# frets-input2.net
KiCad netlist of a schematic drawn in EAGLE
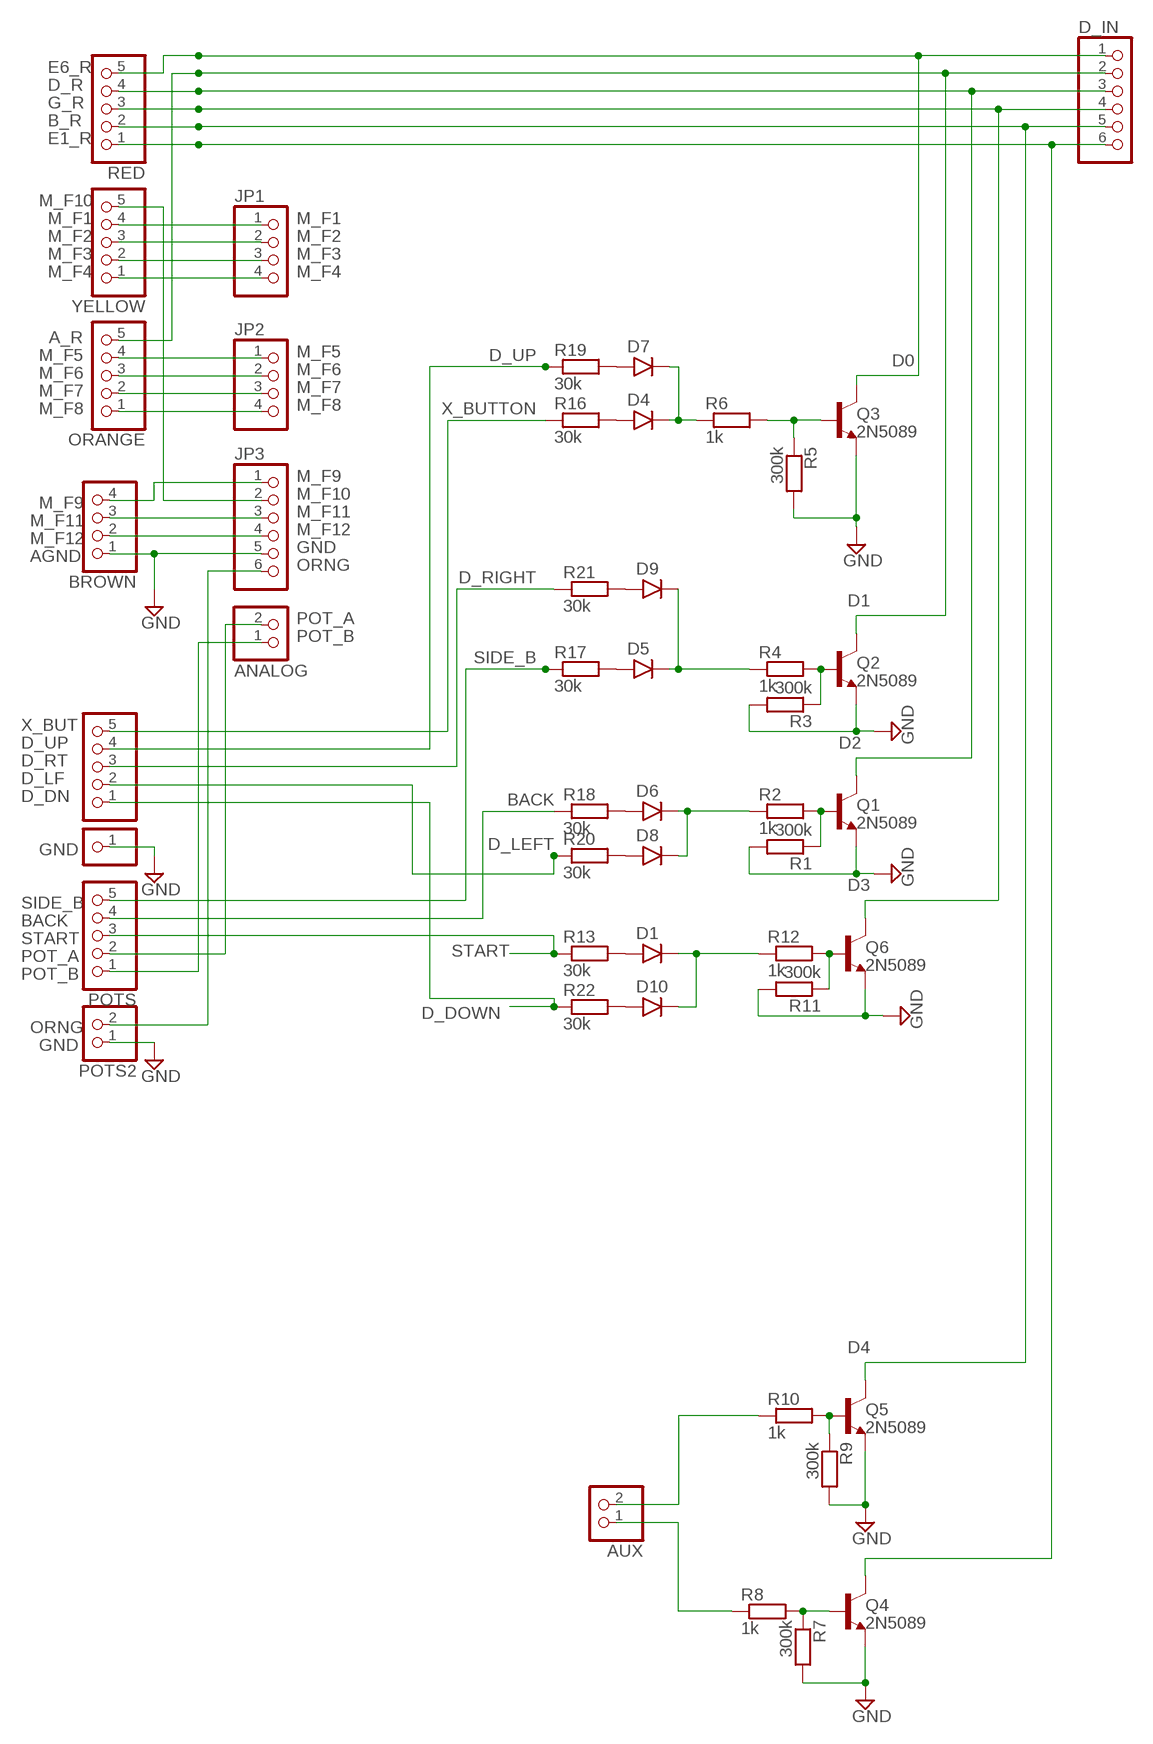
[diagram p0: schematic, sheet 1]

(export (version "E")
  (design (tool "Eeschema 10.0.6"))
  (components
    (comp (ref "ANALOG")
      (value "PINHD-1X2")
      (footprint "eagle-import:1X02")
      (libsource (lib "eagle-import") (part "PINHD-1X2"))
    )
    (comp (ref "AUX")
      (value "PINHD-1X2")
      (footprint "eagle-import:1X02")
      (libsource (lib "eagle-import") (part "PINHD-1X2"))
    )
    (comp (ref "BROWN")
      (value "PINHD-1X4")
      (footprint "eagle-import:1X04")
      (libsource (lib "eagle-import") (part "PINHD-1X4"))
    )
    (comp (ref "D1")
      (value "1N4148-4")
      (footprint "eagle-import:DO35-4")
      (libsource (lib "eagle-import") (part "1N4148-4"))
    )
    (comp (ref "D4")
      (value "1N4148-2")
      (footprint "eagle-import:DO35-2")
      (libsource (lib "eagle-import") (part "1N4148-2"))
    )
    (comp (ref "D5")
      (value "1N4148-4")
      (footprint "eagle-import:DO35-4")
      (libsource (lib "eagle-import") (part "1N4148-4"))
    )
    (comp (ref "D6")
      (value "1N4148-2")
      (footprint "eagle-import:DO35-2")
      (libsource (lib "eagle-import") (part "1N4148-2"))
    )
    (comp (ref "D7")
      (value "1N4148-2")
      (footprint "eagle-import:DO35-2")
      (libsource (lib "eagle-import") (part "1N4148-2"))
    )
    (comp (ref "D8")
      (value "1N4148-2")
      (footprint "eagle-import:DO35-2")
      (libsource (lib "eagle-import") (part "1N4148-2"))
    )
    (comp (ref "D9")
      (value "1N4148-4")
      (footprint "eagle-import:DO35-4")
      (libsource (lib "eagle-import") (part "1N4148-4"))
    )
    (comp (ref "D10")
      (value "1N4148-2")
      (footprint "eagle-import:DO35-2")
      (libsource (lib "eagle-import") (part "1N4148-2"))
    )
    (comp (ref "DPAD")
      (value "PINHD-1X5")
      (footprint "eagle-import:1X05")
      (libsource (lib "eagle-import") (part "PINHD-1X5"))
    )
    (comp (ref "DPAD2")
      (value "PINHD-1X1")
      (footprint "eagle-import:1X01")
      (libsource (lib "eagle-import") (part "PINHD-1X1"))
    )
    (comp (ref "D_IN")
      (value "PINHD-1X6")
      (footprint "eagle-import:1X06")
      (libsource (lib "eagle-import") (part "PINHD-1X6"))
    )
    (comp (ref "JP1")
      (value "PINHD-1X4")
      (footprint "eagle-import:1X04")
      (libsource (lib "eagle-import") (part "PINHD-1X4"))
    )
    (comp (ref "JP2")
      (value "PINHD-1X4")
      (footprint "eagle-import:1X04")
      (libsource (lib "eagle-import") (part "PINHD-1X4"))
    )
    (comp (ref "JP3")
      (value "PINHD-1X6")
      (footprint "eagle-import:1X06")
      (libsource (lib "eagle-import") (part "PINHD-1X6"))
    )
    (comp (ref "ORANGE")
      (value "PINHD-1X5")
      (footprint "eagle-import:1X05")
      (libsource (lib "eagle-import") (part "PINHD-1X5"))
    )
    (comp (ref "POTS")
      (value "PINHD-1X5")
      (footprint "eagle-import:1X05")
      (libsource (lib "eagle-import") (part "PINHD-1X5"))
    )
    (comp (ref "POTS2")
      (value "PINHD-1X2")
      (footprint "eagle-import:1X02")
      (libsource (lib "eagle-import") (part "PINHD-1X2"))
    )
    (comp (ref "Q1")
      (value "2N5089")
      (footprint "eagle-import:TO92-")
      (libsource (lib "eagle-import") (part "2N5089"))
    )
    (comp (ref "Q2")
      (value "2N5089")
      (footprint "eagle-import:TO92-")
      (libsource (lib "eagle-import") (part "2N5089"))
    )
    (comp (ref "Q3")
      (value "2N5089")
      (footprint "eagle-import:TO92-")
      (libsource (lib "eagle-import") (part "2N5089"))
    )
    (comp (ref "Q4")
      (value "2N5089")
      (footprint "eagle-import:TO92-")
      (libsource (lib "eagle-import") (part "2N5089"))
    )
    (comp (ref "Q5")
      (value "2N5089")
      (footprint "eagle-import:TO92-")
      (libsource (lib "eagle-import") (part "2N5089"))
    )
    (comp (ref "Q6")
      (value "2N5089")
      (footprint "eagle-import:TO92-")
      (libsource (lib "eagle-import") (part "2N5089"))
    )
    (comp (ref "R1")
      (value "300k")
      (footprint "eagle-import:R0207_1V")
      (libsource (lib "eagle-import") (part "6MM-EU1"))
    )
    (comp (ref "R2")
      (value "1k")
      (footprint "eagle-import:R0207_3")
      (libsource (lib "eagle-import") (part "6MM-EU"))
    )
    (comp (ref "R3")
      (value "300k")
      (footprint "eagle-import:R0207_1V")
      (libsource (lib "eagle-import") (part "6MM-EU1"))
    )
    (comp (ref "R4")
      (value "1k")
      (footprint "eagle-import:R0207_3")
      (libsource (lib "eagle-import") (part "6MM-EU"))
    )
    (comp (ref "R5")
      (value "300k")
      (footprint "eagle-import:R0207_1V")
      (libsource (lib "eagle-import") (part "6MM-EU1"))
    )
    (comp (ref "R6")
      (value "1k")
      (footprint "eagle-import:R0207_3")
      (libsource (lib "eagle-import") (part "6MM-EU"))
    )
    (comp (ref "R7")
      (value "300k")
      (footprint "eagle-import:R0207_1V")
      (libsource (lib "eagle-import") (part "6MM-EU1"))
    )
    (comp (ref "R8")
      (value "1k")
      (footprint "eagle-import:R0207_3")
      (libsource (lib "eagle-import") (part "6MM-EU"))
    )
    (comp (ref "R9")
      (value "300k")
      (footprint "eagle-import:R0207_1V")
      (libsource (lib "eagle-import") (part "6MM-EU1"))
    )
    (comp (ref "R10")
      (value "1k")
      (footprint "eagle-import:R0207_3")
      (libsource (lib "eagle-import") (part "6MM-EU"))
    )
    (comp (ref "R11")
      (value "300k")
      (footprint "eagle-import:R0207_1V")
      (libsource (lib "eagle-import") (part "6MM-EU1"))
    )
    (comp (ref "R12")
      (value "1k")
      (footprint "eagle-import:R0207_3")
      (libsource (lib "eagle-import") (part "6MM-EU"))
    )
    (comp (ref "R13")
      (value "30k")
      (footprint "eagle-import:R0207_3")
      (libsource (lib "eagle-import") (part "6MM-EU"))
    )
    (comp (ref "R16")
      (value "30k")
      (footprint "eagle-import:R0207_3")
      (libsource (lib "eagle-import") (part "6MM-EU"))
    )
    (comp (ref "R17")
      (value "30k")
      (footprint "eagle-import:R0207_3")
      (libsource (lib "eagle-import") (part "6MM-EU"))
    )
    (comp (ref "R18")
      (value "30k")
      (footprint "eagle-import:R0207_3")
      (libsource (lib "eagle-import") (part "6MM-EU"))
    )
    (comp (ref "R19")
      (value "30k")
      (footprint "eagle-import:R0207_3")
      (libsource (lib "eagle-import") (part "6MM-EU"))
    )
    (comp (ref "R20")
      (value "30k")
      (footprint "eagle-import:R0207_3")
      (libsource (lib "eagle-import") (part "6MM-EU"))
    )
    (comp (ref "R21")
      (value "30k")
      (footprint "eagle-import:R0207_3")
      (libsource (lib "eagle-import") (part "6MM-EU"))
    )
    (comp (ref "R22")
      (value "30k")
      (footprint "eagle-import:R0207_3")
      (libsource (lib "eagle-import") (part "6MM-EU"))
    )
    (comp (ref "RED")
      (value "PINHD-1X5")
      (footprint "eagle-import:1X05")
      (libsource (lib "eagle-import") (part "PINHD-1X5"))
    )
    (comp (ref "YELLOW")
      (value "PINHD-1X5")
      (footprint "eagle-import:1X05")
      (libsource (lib "eagle-import") (part "PINHD-1X5"))
    )
  )
  (nets
    (net (code "1") (name "/BACK") (class "Default")
      (node (ref "POTS") (pin "4") (pinfunction "4_4") (pintype "passive"))
      (node (ref "R18") (pin "1") (pinfunction "1_1") (pintype "passive"))
    )
    (net (code "2") (name "/D0") (class "Default")
      (node (ref "D_IN") (pin "1") (pinfunction "1_1") (pintype "passive"))
      (node (ref "Q3") (pin "1") (pinfunction "C_1") (pintype "passive"))
      (node (ref "RED") (pin "5") (pinfunction "5_5") (pintype "passive"))
    )
    (net (code "3") (name "/D1") (class "Default")
      (node (ref "D_IN") (pin "2") (pinfunction "2_2") (pintype "passive"))
      (node (ref "ORANGE") (pin "5") (pinfunction "5_5") (pintype "passive"))
      (node (ref "Q2") (pin "1") (pinfunction "C_1") (pintype "passive"))
    )
    (net (code "4") (name "/D2") (class "Default")
      (node (ref "D_IN") (pin "3") (pinfunction "3_3") (pintype "passive"))
      (node (ref "Q1") (pin "1") (pinfunction "C_1") (pintype "passive"))
      (node (ref "RED") (pin "4") (pinfunction "4_4") (pintype "passive"))
    )
    (net (code "5") (name "/D3") (class "Default")
      (node (ref "D_IN") (pin "4") (pinfunction "4_4") (pintype "passive"))
      (node (ref "Q6") (pin "1") (pinfunction "C_1") (pintype "passive"))
      (node (ref "RED") (pin "3") (pinfunction "3_3") (pintype "passive"))
    )
    (net (code "6") (name "/D4") (class "Default")
      (node (ref "D_IN") (pin "5") (pinfunction "5_5") (pintype "passive"))
      (node (ref "Q5") (pin "1") (pinfunction "C_1") (pintype "passive"))
      (node (ref "RED") (pin "2") (pinfunction "2_2") (pintype "passive"))
    )
    (net (code "7") (name "/D_DOWN") (class "Default")
      (node (ref "DPAD") (pin "1") (pinfunction "1_1") (pintype "passive"))
      (node (ref "R22") (pin "1") (pinfunction "1_1") (pintype "passive"))
    )
    (net (code "8") (name "/D_LEFT") (class "Default")
      (node (ref "DPAD") (pin "2") (pinfunction "2_2") (pintype "passive"))
      (node (ref "R20") (pin "1") (pinfunction "1_1") (pintype "passive"))
    )
    (net (code "9") (name "/D_RIGHT") (class "Default")
      (node (ref "DPAD") (pin "3") (pinfunction "3_3") (pintype "passive"))
      (node (ref "R21") (pin "1") (pinfunction "1_1") (pintype "passive"))
    )
    (net (code "10") (name "/D_UP") (class "Default")
      (node (ref "DPAD") (pin "4") (pinfunction "4_4") (pintype "passive"))
      (node (ref "R19") (pin "1") (pinfunction "1_1") (pintype "passive"))
    )
    (net (code "11") (name "/M_F1") (class "Default")
      (node (ref "JP1") (pin "1") (pinfunction "1_1") (pintype "passive"))
      (node (ref "YELLOW") (pin "4") (pinfunction "4_4") (pintype "passive"))
    )
    (net (code "12") (name "/M_F2") (class "Default")
      (node (ref "JP1") (pin "2") (pinfunction "2_2") (pintype "passive"))
      (node (ref "YELLOW") (pin "3") (pinfunction "3_3") (pintype "passive"))
    )
    (net (code "13") (name "/M_F3") (class "Default")
      (node (ref "JP1") (pin "3") (pinfunction "3_3") (pintype "passive"))
      (node (ref "YELLOW") (pin "2") (pinfunction "2_2") (pintype "passive"))
    )
    (net (code "14") (name "/M_F4") (class "Default")
      (node (ref "JP1") (pin "4") (pinfunction "4_4") (pintype "passive"))
      (node (ref "YELLOW") (pin "1") (pinfunction "1_1") (pintype "passive"))
    )
    (net (code "15") (name "/M_F5") (class "Default")
      (node (ref "JP2") (pin "1") (pinfunction "1_1") (pintype "passive"))
      (node (ref "ORANGE") (pin "4") (pinfunction "4_4") (pintype "passive"))
    )
    (net (code "16") (name "/M_F6") (class "Default")
      (node (ref "JP2") (pin "2") (pinfunction "2_2") (pintype "passive"))
      (node (ref "ORANGE") (pin "3") (pinfunction "3_3") (pintype "passive"))
    )
    (net (code "17") (name "/M_F7") (class "Default")
      (node (ref "JP2") (pin "3") (pinfunction "3_3") (pintype "passive"))
      (node (ref "ORANGE") (pin "2") (pinfunction "2_2") (pintype "passive"))
    )
    (net (code "18") (name "/M_F8") (class "Default")
      (node (ref "JP2") (pin "4") (pinfunction "4_4") (pintype "passive"))
      (node (ref "ORANGE") (pin "1") (pinfunction "1_1") (pintype "passive"))
    )
    (net (code "19") (name "/M_F9") (class "Default")
      (node (ref "BROWN") (pin "4") (pinfunction "4_4") (pintype "passive"))
      (node (ref "JP3") (pin "1") (pinfunction "1_1") (pintype "passive"))
    )
    (net (code "20") (name "/M_F10") (class "Default")
      (node (ref "JP3") (pin "2") (pinfunction "2_2") (pintype "passive"))
      (node (ref "YELLOW") (pin "5") (pinfunction "5_5") (pintype "passive"))
    )
    (net (code "21") (name "/M_F11") (class "Default")
      (node (ref "BROWN") (pin "3") (pinfunction "3_3") (pintype "passive"))
      (node (ref "JP3") (pin "3") (pinfunction "3_3") (pintype "passive"))
    )
    (net (code "22") (name "/M_F12") (class "Default")
      (node (ref "BROWN") (pin "2") (pinfunction "2_2") (pintype "passive"))
      (node (ref "JP3") (pin "4") (pinfunction "4_4") (pintype "passive"))
    )
    (net (code "23") (name "/ORNG") (class "Default")
      (node (ref "JP3") (pin "6") (pinfunction "6_6") (pintype "passive"))
      (node (ref "POTS2") (pin "2") (pinfunction "2_2") (pintype "passive"))
    )
    (net (code "24") (name "/POT_A") (class "Default")
      (node (ref "ANALOG") (pin "2") (pinfunction "2_2") (pintype "passive"))
      (node (ref "POTS") (pin "2") (pinfunction "2_2") (pintype "passive"))
    )
    (net (code "25") (name "/POT_B") (class "Default")
      (node (ref "ANALOG") (pin "1") (pinfunction "1_1") (pintype "passive"))
      (node (ref "POTS") (pin "1") (pinfunction "1_1") (pintype "passive"))
    )
    (net (code "26") (name "/SIDE_B") (class "Default")
      (node (ref "POTS") (pin "5") (pinfunction "5_5") (pintype "passive"))
      (node (ref "R17") (pin "1") (pinfunction "1_1") (pintype "passive"))
    )
    (net (code "27") (name "/START") (class "Default")
      (node (ref "POTS") (pin "3") (pinfunction "3_3") (pintype "passive"))
      (node (ref "R13") (pin "1") (pinfunction "1_1") (pintype "passive"))
    )
    (net (code "28") (name "/X_BUTTON") (class "Default")
      (node (ref "DPAD") (pin "5") (pinfunction "5_5") (pintype "passive"))
      (node (ref "R16") (pin "1") (pinfunction "1_1") (pintype "passive"))
    )
    (net (code "29") (name "GND") (class "Default")
      (node (ref "BROWN") (pin "1") (pinfunction "1_1") (pintype "passive"))
      (node (ref "DPAD2") (pin "1") (pinfunction "1_1") (pintype "passive"))
      (node (ref "JP3") (pin "5") (pinfunction "5_5") (pintype "passive"))
      (node (ref "POTS2") (pin "1") (pinfunction "1_1") (pintype "passive"))
      (node (ref "Q1") (pin "3") (pinfunction "E_3") (pintype "passive"))
      (node (ref "Q2") (pin "3") (pinfunction "E_3") (pintype "passive"))
      (node (ref "Q3") (pin "3") (pinfunction "E_3") (pintype "passive"))
      (node (ref "Q4") (pin "3") (pinfunction "E_3") (pintype "passive"))
      (node (ref "Q5") (pin "3") (pinfunction "E_3") (pintype "passive"))
      (node (ref "Q6") (pin "3") (pinfunction "E_3") (pintype "passive"))
      (node (ref "R1") (pin "2") (pinfunction "2_2") (pintype "passive"))
      (node (ref "R11") (pin "2") (pinfunction "2_2") (pintype "passive"))
      (node (ref "R3") (pin "2") (pinfunction "2_2") (pintype "passive"))
      (node (ref "R5") (pin "2") (pinfunction "2_2") (pintype "passive"))
      (node (ref "R7") (pin "2") (pinfunction "2_2") (pintype "passive"))
      (node (ref "R9") (pin "2") (pinfunction "2_2") (pintype "passive"))
    )
    (net (code "30") (name "Net-(AUX-Pad1)") (class "Default")
      (node (ref "AUX") (pin "1") (pinfunction "1_1") (pintype "passive"))
      (node (ref "R8") (pin "1") (pinfunction "1_1") (pintype "passive"))
    )
    (net (code "31") (name "Net-(AUX-Pad2)") (class "Default")
      (node (ref "AUX") (pin "2") (pinfunction "2_2") (pintype "passive"))
      (node (ref "R10") (pin "1") (pinfunction "1_1") (pintype "passive"))
    )
    (net (code "32") (name "Net-(D1-PadA)") (class "Default")
      (node (ref "D1") (pin "A") (pinfunction "A_A") (pintype "passive"))
      (node (ref "R13") (pin "2") (pinfunction "2_2") (pintype "passive"))
    )
    (net (code "33") (name "Net-(D1-PadC)") (class "Default")
      (node (ref "D1") (pin "C") (pinfunction "C_C") (pintype "passive"))
      (node (ref "D10") (pin "C") (pinfunction "C_C") (pintype "passive"))
      (node (ref "R12") (pin "1") (pinfunction "1_1") (pintype "passive"))
    )
    (net (code "34") (name "Net-(D4-PadA)") (class "Default")
      (node (ref "D4") (pin "A") (pinfunction "A_A") (pintype "passive"))
      (node (ref "R16") (pin "2") (pinfunction "2_2") (pintype "passive"))
    )
    (net (code "35") (name "Net-(D4-PadC)") (class "Default")
      (node (ref "D4") (pin "C") (pinfunction "C_C") (pintype "passive"))
      (node (ref "D7") (pin "C") (pinfunction "C_C") (pintype "passive"))
      (node (ref "R6") (pin "1") (pinfunction "1_1") (pintype "passive"))
    )
    (net (code "36") (name "Net-(D5-PadA)") (class "Default")
      (node (ref "D5") (pin "A") (pinfunction "A_A") (pintype "passive"))
      (node (ref "R17") (pin "2") (pinfunction "2_2") (pintype "passive"))
    )
    (net (code "37") (name "Net-(D5-PadC)") (class "Default")
      (node (ref "D5") (pin "C") (pinfunction "C_C") (pintype "passive"))
      (node (ref "D9") (pin "C") (pinfunction "C_C") (pintype "passive"))
      (node (ref "R4") (pin "1") (pinfunction "1_1") (pintype "passive"))
    )
    (net (code "38") (name "Net-(D6-PadA)") (class "Default")
      (node (ref "D6") (pin "A") (pinfunction "A_A") (pintype "passive"))
      (node (ref "R18") (pin "2") (pinfunction "2_2") (pintype "passive"))
    )
    (net (code "39") (name "Net-(D6-PadC)") (class "Default")
      (node (ref "D6") (pin "C") (pinfunction "C_C") (pintype "passive"))
      (node (ref "D8") (pin "C") (pinfunction "C_C") (pintype "passive"))
      (node (ref "R2") (pin "1") (pinfunction "1_1") (pintype "passive"))
    )
    (net (code "40") (name "Net-(D7-PadA)") (class "Default")
      (node (ref "D7") (pin "A") (pinfunction "A_A") (pintype "passive"))
      (node (ref "R19") (pin "2") (pinfunction "2_2") (pintype "passive"))
    )
    (net (code "41") (name "Net-(D8-PadA)") (class "Default")
      (node (ref "D8") (pin "A") (pinfunction "A_A") (pintype "passive"))
      (node (ref "R20") (pin "2") (pinfunction "2_2") (pintype "passive"))
    )
    (net (code "42") (name "Net-(D9-PadA)") (class "Default")
      (node (ref "D9") (pin "A") (pinfunction "A_A") (pintype "passive"))
      (node (ref "R21") (pin "2") (pinfunction "2_2") (pintype "passive"))
    )
    (net (code "43") (name "Net-(D10-PadA)") (class "Default")
      (node (ref "D10") (pin "A") (pinfunction "A_A") (pintype "passive"))
      (node (ref "R22") (pin "2") (pinfunction "2_2") (pintype "passive"))
    )
    (net (code "44") (name "Net-(Q1-B)") (class "Default")
      (node (ref "Q1") (pin "2") (pinfunction "B_2") (pintype "passive"))
      (node (ref "R1") (pin "1") (pinfunction "1_1") (pintype "passive"))
      (node (ref "R2") (pin "2") (pinfunction "2_2") (pintype "passive"))
    )
    (net (code "45") (name "Net-(Q2-B)") (class "Default")
      (node (ref "Q2") (pin "2") (pinfunction "B_2") (pintype "passive"))
      (node (ref "R3") (pin "1") (pinfunction "1_1") (pintype "passive"))
      (node (ref "R4") (pin "2") (pinfunction "2_2") (pintype "passive"))
    )
    (net (code "46") (name "Net-(Q3-B)") (class "Default")
      (node (ref "Q3") (pin "2") (pinfunction "B_2") (pintype "passive"))
      (node (ref "R5") (pin "1") (pinfunction "1_1") (pintype "passive"))
      (node (ref "R6") (pin "2") (pinfunction "2_2") (pintype "passive"))
    )
    (net (code "47") (name "Net-(Q4-B)") (class "Default")
      (node (ref "Q4") (pin "2") (pinfunction "B_2") (pintype "passive"))
      (node (ref "R7") (pin "1") (pinfunction "1_1") (pintype "passive"))
      (node (ref "R8") (pin "2") (pinfunction "2_2") (pintype "passive"))
    )
    (net (code "48") (name "Net-(Q4-C)") (class "Default")
      (node (ref "D_IN") (pin "6") (pinfunction "6_6") (pintype "passive"))
      (node (ref "Q4") (pin "1") (pinfunction "C_1") (pintype "passive"))
      (node (ref "RED") (pin "1") (pinfunction "1_1") (pintype "passive"))
    )
    (net (code "49") (name "Net-(Q5-B)") (class "Default")
      (node (ref "Q5") (pin "2") (pinfunction "B_2") (pintype "passive"))
      (node (ref "R10") (pin "2") (pinfunction "2_2") (pintype "passive"))
      (node (ref "R9") (pin "1") (pinfunction "1_1") (pintype "passive"))
    )
    (net (code "50") (name "Net-(Q6-B)") (class "Default")
      (node (ref "Q6") (pin "2") (pinfunction "B_2") (pintype "passive"))
      (node (ref "R11") (pin "1") (pinfunction "1_1") (pintype "passive"))
      (node (ref "R12") (pin "2") (pinfunction "2_2") (pintype "passive"))
    )
  )
)
